# tuch-tara-ir.net
KiCad netlist of a schematic drawn in Altium Designer
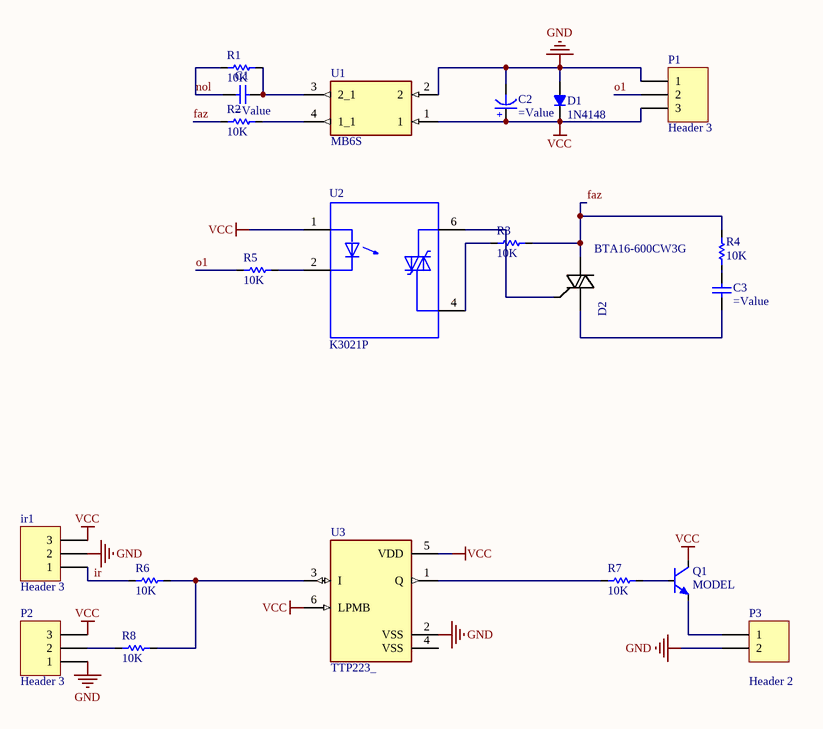
[diagram p0: tuch-tara-ir.SchDoc]

(export (version "E")
  (design (tool "Eeschema 10.0.6"))
  (components
    (comp (ref "C1")
      (value "~")
      (footprint "CAP-30")
      (description "Capacitor")
      (libsource (lib "AltiumLib1") (part "Capacitor"))
    )
    (comp (ref "C2")
      (value "~")
      (footprint "ELEC-CAP-RAD10-20")
      (description "Electrolytic Capacitor")
      (libsource (lib "AltiumLib1") (part "Capacitor Electrolytic"))
    )
    (comp (ref "C3")
      (value "~")
      (footprint "CAP-30")
      (description "Capacitor")
      (libsource (lib "AltiumLib1") (part "Capacitor"))
    )
    (comp (ref "D1")
      (value "MODEL")
      (footprint "DO-41")
      (description "Diode")
      (fields (field (name "MODEL") "1N4148"))
      (libsource (lib "AltiumLib1") (part "Diode"))
    )
    (comp (ref "D2")
      (value "BTA16-600CW3G")
      (footprint "*TO254P1028X482X1968-3")
      (description "TRIAC Standard 600V 16A Through Hole TO-220AB")
      (fields (field (name "MF") "Littelfuse Inc."))
      (libsource (lib "BTA16-600CW3G") (part "BTA16-600CW3G"))
    )
    (comp (ref "ir1")
      (value "Header 3")
      (footprint "HDR1X3")
      (description "Header, 3-Pin")
      (fields (field (name "PUBLISHER") "Altium Limited"))
      (libsource (lib "Miscellaneous Connectors") (part "Header 3"))
    )
    (comp (ref "P1")
      (value "Header 3")
      (footprint "HDR1X3")
      (description "Header, 3-Pin")
      (fields (field (name "PUBLISHER") "Altium Limited"))
      (libsource (lib "") (part "Header 3_1"))
    )
    (comp (ref "P2")
      (value "Header 3")
      (footprint "HDR1X3")
      (description "Header, 3-Pin")
      (fields (field (name "PUBLISHER") "Altium Limited"))
      (libsource (lib "Miscellaneous Connectors") (part "Header 3"))
    )
    (comp (ref "P3")
      (value "Header 2")
      (footprint "HDR1X2")
      (description "Header, 2-Pin")
      (fields (field (name "PUBLISHER") "Altium Limited"))
      (libsource (lib "Miscellaneous Connectors") (part "Header 2"))
    )
    (comp (ref "Q1")
      (value "MODEL")
      (footprint "SOT32")
      (description "NPN Bipolar Transistor")
      (libsource (lib "AltiumLib1") (part "BD139"))
    )
    (comp (ref "R1")
      (value "10K")
      (footprint "Res-(1/4)")
      (description "Resistor")
      (fields (field (name "TOLERANCE") "5%") (field (name "POWER") "1/4 W"))
      (libsource (lib "AltiumLib1") (part "Resistor"))
    )
    (comp (ref "R2")
      (value "10K")
      (footprint "Res-(1/4)")
      (description "Resistor")
      (fields (field (name "TOLERANCE") "5%") (field (name "POWER") "1/4 W"))
      (libsource (lib "AltiumLib1") (part "Resistor"))
    )
    (comp (ref "R3")
      (value "10K")
      (footprint "RES 1206 (3216X08L)")
      (description "Resistor")
      (fields (field (name "TOLERANCE") "5%") (field (name "POWER") "1/4 W"))
      (libsource (lib "AltiumLib1") (part "Resistor"))
    )
    (comp (ref "R4")
      (value "10K")
      (footprint "RES 1206 (3216X08L)")
      (description "Resistor")
      (fields (field (name "TOLERANCE") "5%") (field (name "POWER") "1/4 W"))
      (libsource (lib "AltiumLib1") (part "Resistor"))
    )
    (comp (ref "R5")
      (value "10K")
      (footprint "RES 1206 (3216X08L)")
      (description "Resistor")
      (fields (field (name "TOLERANCE") "5%") (field (name "POWER") "1/4 W"))
      (libsource (lib "AltiumLib1") (part "Resistor"))
    )
    (comp (ref "R6")
      (value "10K")
      (footprint "RES 0805 (2012X06L)")
      (description "Resistor")
      (fields (field (name "TOLERANCE") "5%") (field (name "POWER") "1/4 W"))
      (libsource (lib "AltiumLib1") (part "Resistor"))
    )
    (comp (ref "R7")
      (value "10K")
      (footprint "RES 0805 (2012X06L)")
      (description "Resistor")
      (fields (field (name "TOLERANCE") "5%") (field (name "POWER") "1/4 W"))
      (libsource (lib "AltiumLib1") (part "Resistor"))
    )
    (comp (ref "R8")
      (value "10K")
      (footprint "RES 0805 (2012X06L)")
      (description "Resistor")
      (fields (field (name "TOLERANCE") "5%") (field (name "POWER") "1/4 W"))
      (libsource (lib "AltiumLib1") (part "Resistor"))
    )
    (comp (ref "U1")
      (value "MB6S")
      (footprint "SOIC245P670X270-4N")
      (description "Bridge Rectifier Single Phase Standard 600V Surface Mount 4-SOIC")
      (fields (field (name "MF") "ON Semiconductor") (field (name "DIGI-KEY_PART_NUMBER") "MB6SCT-ND"))
      (libsource (lib "MB6S") (part "MB6S"))
    )
    (comp (ref "U2")
      (value "K3021P")
      (footprint "DIP762W50P254L730H410Q6")
      (description "Optoisolator Triac Output 5300Vrms 1 Channel 6-DIP")
      (fields (field (name "MF") "Vishay Semiconductor"))
      (libsource (lib "K3021P") (part "K3021P"))
    )
    (comp (ref "U3")
      (value "TTP223_")
      (footprint "SOT95P285X126-6N")
      (fields (field (name "MP") "TTP223") (field (name "MF") "KOA Speer"))
      (libsource (lib "TTP223_") (part "TTP223_"))
    )
  )
  (nets
    (net (code "1") (name "/faz") (class "Default")
      (node (ref "D2") (pin "2") (pinfunction "MT2_2") (pintype "passive"))
      (node (ref "R2") (pin "2") (pinfunction "2_2") (pintype "passive"))
      (node (ref "R3") (pin "2") (pinfunction "2_2") (pintype "passive"))
      (node (ref "R4") (pin "2") (pinfunction "2_2") (pintype "passive"))
    )
    (net (code "2") (name "/ir") (class "Default")
      (node (ref "R6") (pin "1") (pinfunction "1_1") (pintype "passive"))
      (node (ref "ir1") (pin "1") (pinfunction "1_1") (pintype "passive"))
    )
    (net (code "3") (name "/nol") (class "Default")
      (node (ref "C1") (pin "1") (pinfunction "+_1") (pintype "passive"))
      (node (ref "R1") (pin "2") (pinfunction "2_2") (pintype "passive"))
    )
    (net (code "4") (name "/o1") (class "Default")
      (node (ref "P1") (pin "2") (pinfunction "2_2") (pintype "passive"))
      (node (ref "R5") (pin "1") (pinfunction "1_1") (pintype "passive"))
    )
    (net (code "5") (name "GND") (class "Default")
      (node (ref "C2") (pin "1") (pinfunction "-_1") (pintype "passive"))
      (node (ref "D1") (pin "1") (pinfunction "A_1") (pintype "passive"))
      (node (ref "P1") (pin "1") (pinfunction "1_1") (pintype "passive"))
      (node (ref "P2") (pin "1") (pinfunction "1_1") (pintype "passive"))
      (node (ref "P3") (pin "2") (pinfunction "2_2") (pintype "passive"))
      (node (ref "U1") (pin "2") (pinfunction "2_2") (pintype "input"))
      (node (ref "U3") (pin "2") (pinfunction "VSS_2") (pintype "power_in"))
      (node (ref "ir1") (pin "2") (pinfunction "2_2") (pintype "passive"))
    )
    (net (code "6") (name "Net-(C1--)") (class "Default")
      (node (ref "C1") (pin "2") (pinfunction "-_2") (pintype "passive"))
      (node (ref "R1") (pin "1") (pinfunction "1_1") (pintype "passive"))
      (node (ref "U1") (pin "3") (pinfunction "2_1_3") (pintype "output"))
    )
    (net (code "7") (name "Net-(C3-+)") (class "Default")
      (node (ref "C3") (pin "1") (pinfunction "+_1") (pintype "passive"))
      (node (ref "D2") (pin "1") (pinfunction "MT1_1") (pintype "passive"))
    )
    (net (code "8") (name "Net-(C3--)") (class "Default")
      (node (ref "C3") (pin "2") (pinfunction "-_2") (pintype "passive"))
      (node (ref "R4") (pin "1") (pinfunction "1_1") (pintype "passive"))
    )
    (net (code "9") (name "Net-(D2-G)") (class "Default")
      (node (ref "D2") (pin "3") (pinfunction "G_3") (pintype "passive"))
      (node (ref "U2") (pin "6") (pinfunction "MT2_6") (pintype "passive"))
    )
    (net (code "10") (name "Net-(P2-Pad2)") (class "Default")
      (node (ref "P2") (pin "2") (pinfunction "2_2") (pintype "passive"))
      (node (ref "R8") (pin "1") (pinfunction "1_1") (pintype "passive"))
    )
    (net (code "11") (name "Net-(Q1-B)") (class "Default")
      (node (ref "Q1") (pin "3") (pinfunction "B_3") (pintype "passive"))
      (node (ref "R7") (pin "2") (pinfunction "2_2") (pintype "passive"))
    )
    (net (code "12") (name "Net-(Q1-E)") (class "Default")
      (node (ref "P3") (pin "1") (pinfunction "1_1") (pintype "passive"))
      (node (ref "Q1") (pin "1") (pinfunction "E_1") (pintype "passive"))
    )
    (net (code "13") (name "Net-(U1-1_1)") (class "Default")
      (node (ref "R2") (pin "1") (pinfunction "1_1") (pintype "passive"))
      (node (ref "U1") (pin "4") (pinfunction "1_1_4") (pintype "output"))
    )
    (net (code "14") (name "Net-(U2-C)") (class "Default")
      (node (ref "R5") (pin "2") (pinfunction "2_2") (pintype "passive"))
      (node (ref "U2") (pin "2") (pinfunction "C_2") (pintype "passive"))
    )
    (net (code "15") (name "Net-(U2-MT1)") (class "Default")
      (node (ref "R3") (pin "1") (pinfunction "1_1") (pintype "passive"))
      (node (ref "U2") (pin "4") (pinfunction "MT1_4") (pintype "passive"))
    )
    (net (code "16") (name "Net-(U3-I)") (class "Default")
      (node (ref "R6") (pin "2") (pinfunction "2_2") (pintype "passive"))
      (node (ref "R8") (pin "2") (pinfunction "2_2") (pintype "passive"))
      (node (ref "U3") (pin "3") (pinfunction "I_3") (pintype "bidirectional"))
    )
    (net (code "17") (name "Net-(U3-Q)") (class "Default")
      (node (ref "R7") (pin "1") (pinfunction "1_1") (pintype "passive"))
      (node (ref "U3") (pin "1") (pinfunction "Q_1") (pintype "output"))
    )
    (net (code "18") (name "VCC") (class "Default")
      (node (ref "C2") (pin "2") (pinfunction "+_2") (pintype "passive"))
      (node (ref "D1") (pin "2") (pinfunction "K_2") (pintype "passive"))
      (node (ref "P1") (pin "3") (pinfunction "3_3") (pintype "passive"))
      (node (ref "P2") (pin "3") (pinfunction "3_3") (pintype "passive"))
      (node (ref "Q1") (pin "2") (pinfunction "C_2") (pintype "passive"))
      (node (ref "U1") (pin "1") (pinfunction "1_1") (pintype "input"))
      (node (ref "U2") (pin "1") (pinfunction "A_1") (pintype "passive"))
      (node (ref "U3") (pin "5") (pinfunction "VDD_5") (pintype "power_in"))
      (node (ref "U3") (pin "6") (pinfunction "LPMB_6") (pintype "input"))
      (node (ref "ir1") (pin "3") (pinfunction "3_3") (pintype "passive"))
    )
    (net (code "19") (name "unconnected-(U3-VSS-Pad4)") (class "Default")
      (node (ref "U3") (pin "4") (pinfunction "VSS_4") (pintype "power_in"))
    )
  )
)
